# LedDisp.net
KiCad netlist of a schematic drawn in Altium Designer
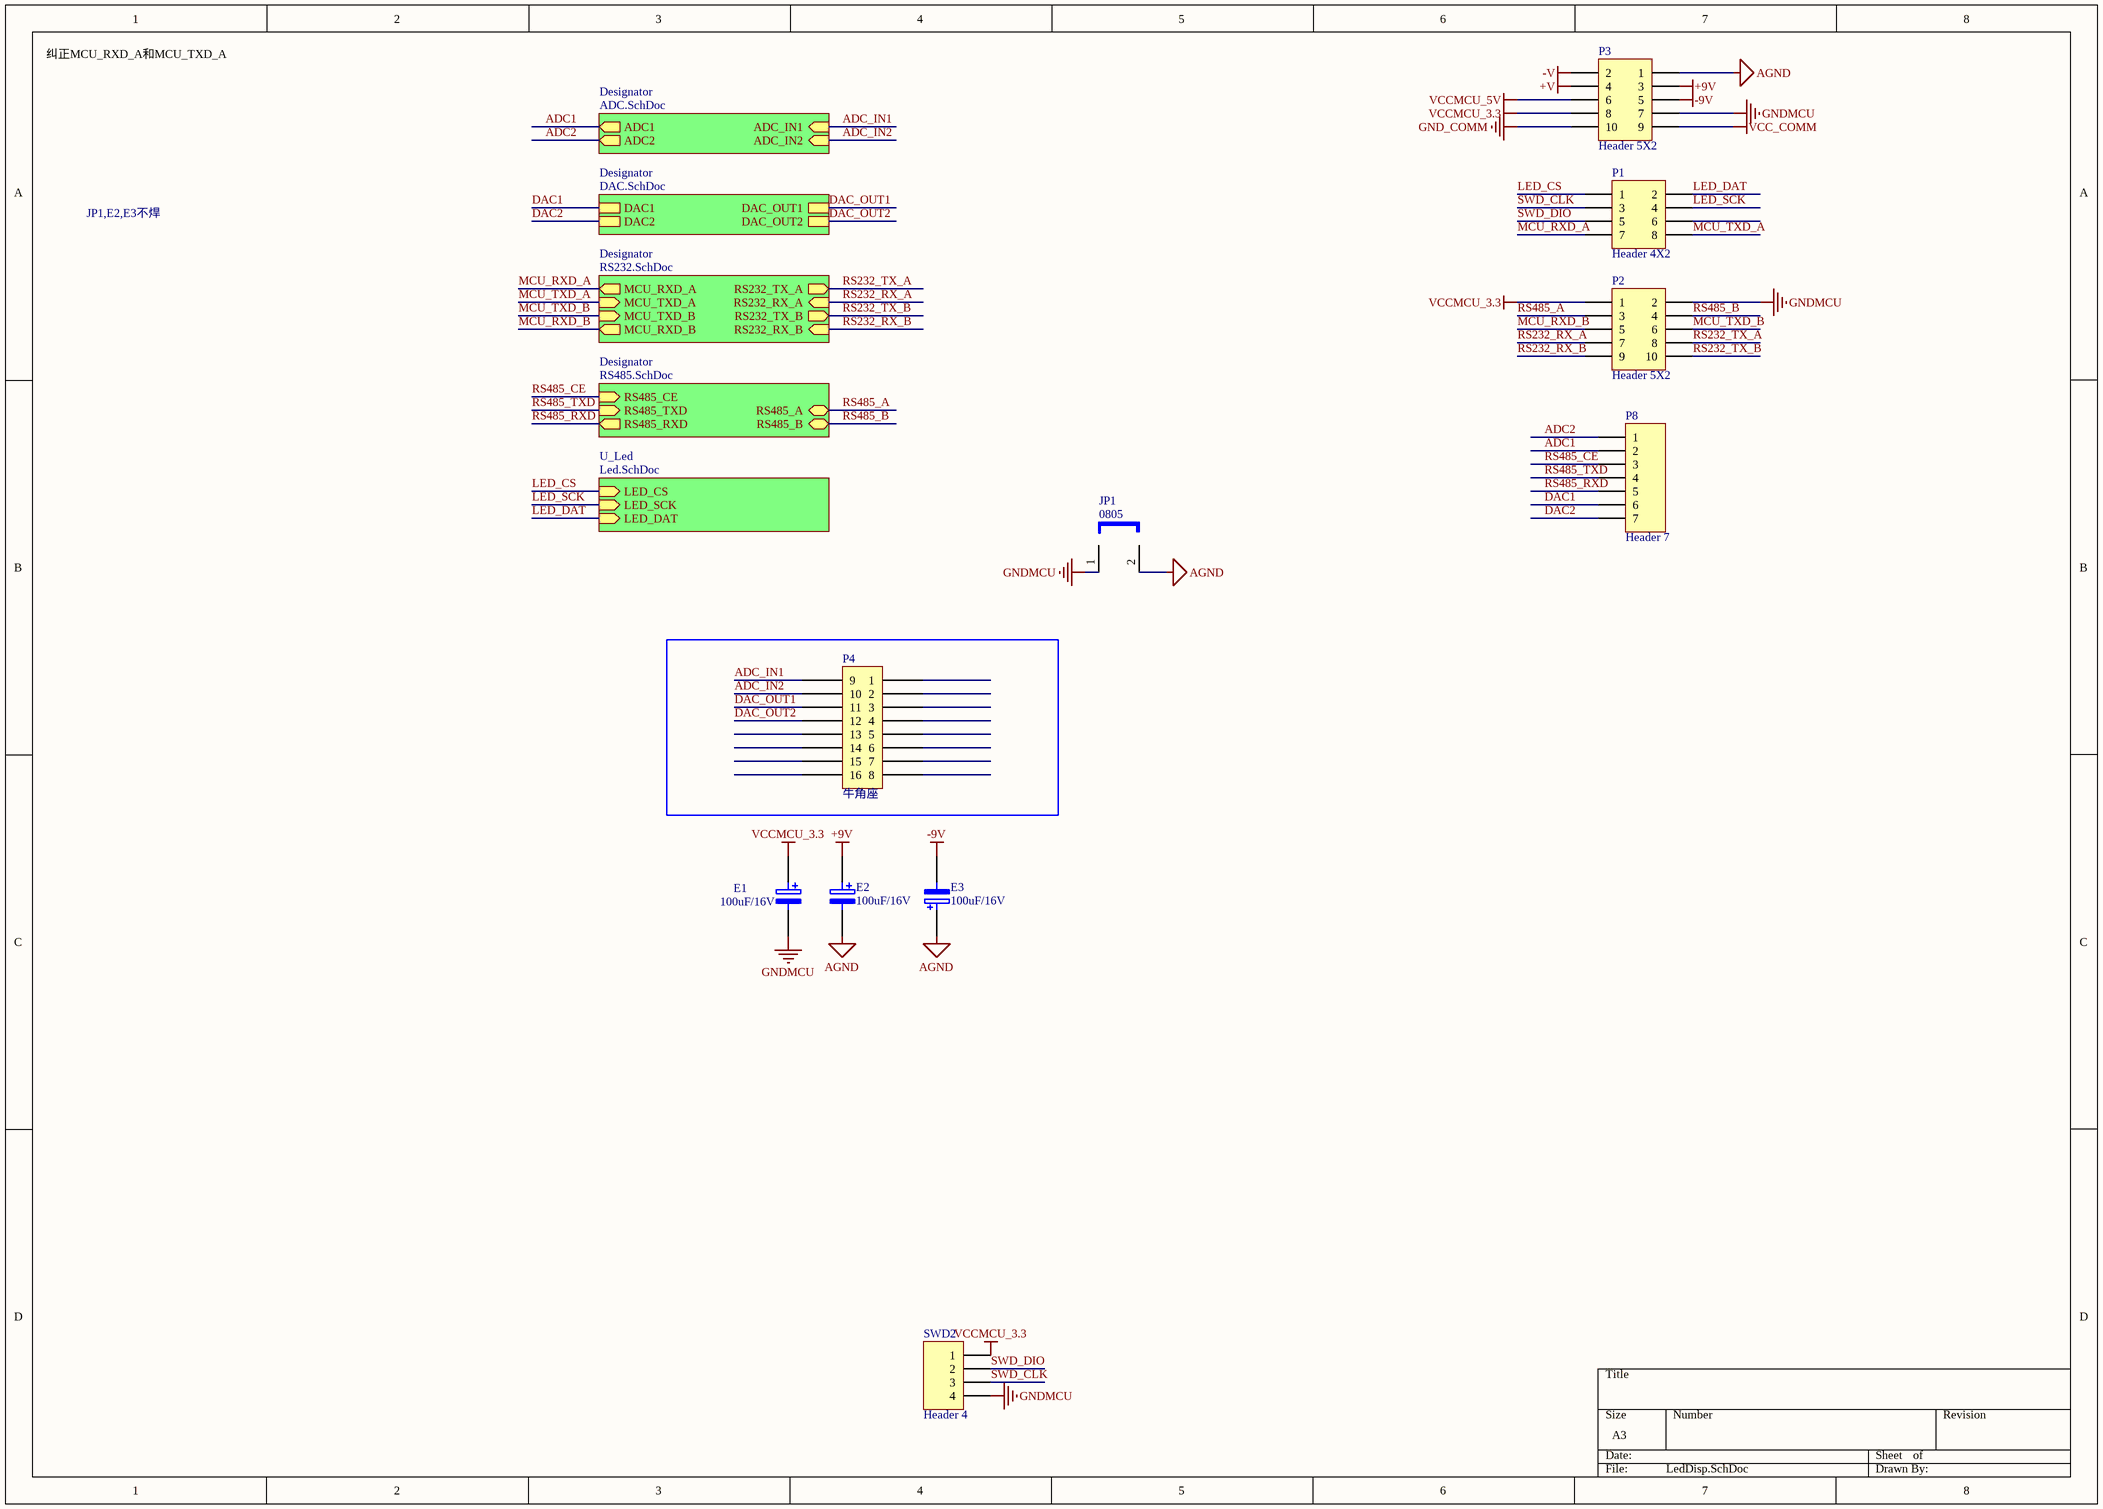
[diagram p0: LedDisp.SchDoc]

(export (version "E")
  (design (tool "Eeschema 10.0.6"))
  (components
    (comp (ref "E1")
      (value "100uF/16V")
      (footprint "C-10UF")
      (description "Electrolytic Capacitor")
      (libsource (lib "YGInfoSCHLib") (part "ELECTRO2"))
    )
    (comp (ref "E2")
      (value "100uF/16V")
      (footprint "C-10UF")
      (description "Electrolytic Capacitor")
      (libsource (lib "YGInfoSCHLib") (part "ELECTRO2"))
    )
    (comp (ref "E3")
      (value "100uF/16V")
      (footprint "C-10UF")
      (description "Electrolytic Capacitor")
      (libsource (lib "YGInfoSCHLib") (part "ELECTRO2"))
    )
    (comp (ref "JP1")
      (value "0805")
      (footprint "RESC_E0805_2012X50N")
      (description "Jumper")
      (libsource (lib "YGInfoSCHLib") (part "JUMPER"))
    )
    (comp (ref "P1")
      (value "Header 4X2")
      (footprint "HDR2X4")
      (description "Header, 4-Pin, Dual row")
      (fields (field (name "PUBLISHER") "Altium Limited"))
      (libsource (lib "YGInfoSCHLib") (part "Header 4X2"))
    )
    (comp (ref "P2")
      (value "Header 5X2")
      (footprint "HDR2X5")
      (description "Header, 5-Pin, Dual row")
      (fields (field (name "PUBLISHER") "Altium Limited"))
      (libsource (lib "") (part "Header 5X2_1"))
    )
    (comp (ref "P3")
      (value "Header 5X2")
      (footprint "HDR2X5")
      (description "Header, 5-Pin, Dual row")
      (fields (field (name "PUBLISHER") "Altium Limited"))
      (libsource (lib "YGInfoSCHLib") (part "Header 5X2"))
    )
    (comp (ref "P4") (value "牛角座") (footprint "2.54* 2*8p") (libsource (lib "YGInfoSCHLib") (part "CON2*8")))
    (comp (ref "P8")
      (value "Header 7")
      (footprint "HDR1X7")
      (description "Header, 7-Pin")
      (fields (field (name "PUBLISHER") "Altium Limited"))
      (libsource (lib "YGInfoSCHLib") (part "Header 7"))
    )
    (comp (ref "SWD2")
      (value "Header 4")
      (footprint "HDR1X4")
      (description "Header, 4-Pin")
      (fields (field (name "PUBLISHER") "Altium Limited"))
      (libsource (lib "YGInfoSCHLib") (part "Header 4"))
    )
  )
  (nets
    (net (code "1") (name "+9V") (class "Default")
      (node (ref "E2") (pin "1") (pinfunction "1_1") (pintype "passive"))
      (node (ref "P3") (pin "3") (pinfunction "3_3") (pintype "passive"))
    )
    (net (code "2") (name "+V") (class "Default")
      (node (ref "P3") (pin "4") (pinfunction "4_4") (pintype "passive"))
    )
    (net (code "3") (name "-9V") (class "Default")
      (node (ref "E3") (pin "2") (pinfunction "2_2") (pintype "passive"))
      (node (ref "P3") (pin "5") (pinfunction "5_5") (pintype "passive"))
    )
    (net (code "4") (name "-V") (class "Default")
      (node (ref "P3") (pin "2") (pinfunction "2_2") (pintype "passive"))
    )
    (net (code "5") (name "/ADC1") (class "Default")
      (node (ref "P8") (pin "2") (pinfunction "2_2") (pintype "passive"))
    )
    (net (code "6") (name "/ADC2") (class "Default")
      (node (ref "P8") (pin "1") (pinfunction "1_1") (pintype "passive"))
    )
    (net (code "7") (name "/ADC_IN1") (class "Default")
      (node (ref "P4") (pin "9") (pinfunction "9_9") (pintype "passive"))
    )
    (net (code "8") (name "/ADC_IN2") (class "Default")
      (node (ref "P4") (pin "10") (pinfunction "10_10") (pintype "passive"))
    )
    (net (code "9") (name "/DAC1") (class "Default")
      (node (ref "P8") (pin "6") (pinfunction "6_6") (pintype "passive"))
    )
    (net (code "10") (name "/DAC2") (class "Default")
      (node (ref "P8") (pin "7") (pinfunction "7_7") (pintype "passive"))
    )
    (net (code "11") (name "/DAC_OUT1") (class "Default")
      (node (ref "P4") (pin "11") (pinfunction "11_11") (pintype "passive"))
    )
    (net (code "12") (name "/DAC_OUT2") (class "Default")
      (node (ref "P4") (pin "12") (pinfunction "12_12") (pintype "passive"))
    )
    (net (code "13") (name "/LED_CS") (class "Default")
      (node (ref "P1") (pin "1") (pinfunction "1_1") (pintype "passive"))
    )
    (net (code "14") (name "/LED_DAT") (class "Default")
      (node (ref "P1") (pin "2") (pinfunction "2_2") (pintype "passive"))
    )
    (net (code "15") (name "/LED_SCK") (class "Default")
      (node (ref "P1") (pin "4") (pinfunction "4_4") (pintype "passive"))
    )
    (net (code "16") (name "/MCU_RXD_A") (class "Default")
      (node (ref "P1") (pin "7") (pinfunction "7_7") (pintype "passive"))
    )
    (net (code "17") (name "/MCU_RXD_B") (class "Default")
      (node (ref "P2") (pin "5") (pinfunction "5_5") (pintype "passive"))
    )
    (net (code "18") (name "/MCU_TXD_A") (class "Default")
      (node (ref "P1") (pin "8") (pinfunction "8_8") (pintype "passive"))
    )
    (net (code "19") (name "/MCU_TXD_B") (class "Default")
      (node (ref "P2") (pin "6") (pinfunction "6_6") (pintype "passive"))
    )
    (net (code "20") (name "/RS232_RX_A") (class "Default")
      (node (ref "P2") (pin "7") (pinfunction "7_7") (pintype "passive"))
    )
    (net (code "21") (name "/RS232_RX_B") (class "Default")
      (node (ref "P2") (pin "9") (pinfunction "9_9") (pintype "passive"))
    )
    (net (code "22") (name "/RS232_TX_A") (class "Default")
      (node (ref "P2") (pin "8") (pinfunction "8_8") (pintype "passive"))
    )
    (net (code "23") (name "/RS232_TX_B") (class "Default")
      (node (ref "P2") (pin "10") (pinfunction "10_10") (pintype "passive"))
    )
    (net (code "24") (name "/RS485_A") (class "Default")
      (node (ref "P2") (pin "3") (pinfunction "3_3") (pintype "passive"))
    )
    (net (code "25") (name "/RS485_B") (class "Default")
      (node (ref "P2") (pin "4") (pinfunction "4_4") (pintype "passive"))
    )
    (net (code "26") (name "/RS485_CE") (class "Default")
      (node (ref "P8") (pin "3") (pinfunction "3_3") (pintype "passive"))
    )
    (net (code "27") (name "/RS485_RXD") (class "Default")
      (node (ref "P8") (pin "5") (pinfunction "5_5") (pintype "passive"))
    )
    (net (code "28") (name "/RS485_TXD") (class "Default")
      (node (ref "P8") (pin "4") (pinfunction "4_4") (pintype "passive"))
    )
    (net (code "29") (name "/SWD_CLK") (class "Default")
      (node (ref "P1") (pin "3") (pinfunction "3_3") (pintype "passive"))
      (node (ref "SWD2") (pin "3") (pinfunction "3_3") (pintype "passive"))
    )
    (net (code "30") (name "/SWD_DIO") (class "Default")
      (node (ref "P1") (pin "5") (pinfunction "5_5") (pintype "passive"))
      (node (ref "SWD2") (pin "2") (pinfunction "2_2") (pintype "passive"))
    )
    (net (code "31") (name "AGND") (class "Default")
      (node (ref "E2") (pin "2") (pinfunction "2_2") (pintype "passive"))
      (node (ref "E3") (pin "1") (pinfunction "1_1") (pintype "passive"))
      (node (ref "JP1") (pin "2") (pinfunction "2_2") (pintype "passive"))
      (node (ref "P3") (pin "1") (pinfunction "1_1") (pintype "passive"))
    )
    (net (code "32") (name "GNDMCU") (class "Default")
      (node (ref "E1") (pin "2") (pinfunction "2_2") (pintype "passive"))
      (node (ref "JP1") (pin "1") (pinfunction "1_1") (pintype "passive"))
      (node (ref "P2") (pin "2") (pinfunction "2_2") (pintype "passive"))
      (node (ref "P3") (pin "7") (pinfunction "7_7") (pintype "passive"))
      (node (ref "SWD2") (pin "4") (pinfunction "4_4") (pintype "passive"))
    )
    (net (code "33") (name "GND_COMM") (class "Default")
      (node (ref "P3") (pin "10") (pinfunction "10_10") (pintype "passive"))
    )
    (net (code "34") (name "VCCMCU_3.3") (class "Default")
      (node (ref "E1") (pin "1") (pinfunction "1_1") (pintype "passive"))
      (node (ref "P2") (pin "1") (pinfunction "1_1") (pintype "passive"))
      (node (ref "P3") (pin "8") (pinfunction "8_8") (pintype "passive"))
      (node (ref "SWD2") (pin "1") (pinfunction "1_1") (pintype "passive"))
    )
    (net (code "35") (name "VCCMCU_5V") (class "Default")
      (node (ref "P3") (pin "6") (pinfunction "6_6") (pintype "passive"))
    )
    (net (code "36") (name "VCC_COMM") (class "Default")
      (node (ref "P3") (pin "9") (pinfunction "9_9") (pintype "passive"))
    )
    (net (code "37") (name "unconnected-(P1-Pad6)") (class "Default")
      (node (ref "P1") (pin "6") (pinfunction "6_6") (pintype "passive"))
    )
    (net (code "38") (name "unconnected-(P4-Pad1)") (class "Default")
      (node (ref "P4") (pin "1") (pinfunction "1_1") (pintype "power_in"))
    )
    (net (code "39") (name "unconnected-(P4-Pad2)") (class "Default")
      (node (ref "P4") (pin "2") (pinfunction "2_2") (pintype "passive"))
    )
    (net (code "40") (name "unconnected-(P4-Pad3)") (class "Default")
      (node (ref "P4") (pin "3") (pinfunction "3_3") (pintype "passive"))
    )
    (net (code "41") (name "unconnected-(P4-Pad4)") (class "Default")
      (node (ref "P4") (pin "4") (pinfunction "4_4") (pintype "passive"))
    )
    (net (code "42") (name "unconnected-(P4-Pad5)") (class "Default")
      (node (ref "P4") (pin "5") (pinfunction "5_5") (pintype "passive"))
    )
    (net (code "43") (name "unconnected-(P4-Pad6)") (class "Default")
      (node (ref "P4") (pin "6") (pinfunction "6_6") (pintype "passive"))
    )
    (net (code "44") (name "unconnected-(P4-Pad7)") (class "Default")
      (node (ref "P4") (pin "7") (pinfunction "7_7") (pintype "passive"))
    )
    (net (code "45") (name "unconnected-(P4-Pad8)") (class "Default")
      (node (ref "P4") (pin "8") (pinfunction "8_8") (pintype "passive"))
    )
    (net (code "46") (name "unconnected-(P4-Pad13)") (class "Default")
      (node (ref "P4") (pin "13") (pinfunction "13_13") (pintype "passive"))
    )
    (net (code "47") (name "unconnected-(P4-Pad14)") (class "Default")
      (node (ref "P4") (pin "14") (pinfunction "14_14") (pintype "passive"))
    )
    (net (code "48") (name "unconnected-(P4-Pad15)") (class "Default")
      (node (ref "P4") (pin "15") (pinfunction "15_15") (pintype "passive"))
    )
    (net (code "49") (name "unconnected-(P4-Pad16)") (class "Default")
      (node (ref "P4") (pin "16") (pinfunction "16_16") (pintype "passive"))
    )
  )
)
